# asu_racing_team_solo.net
KiCad netlist of a schematic drawn in Altium Designer
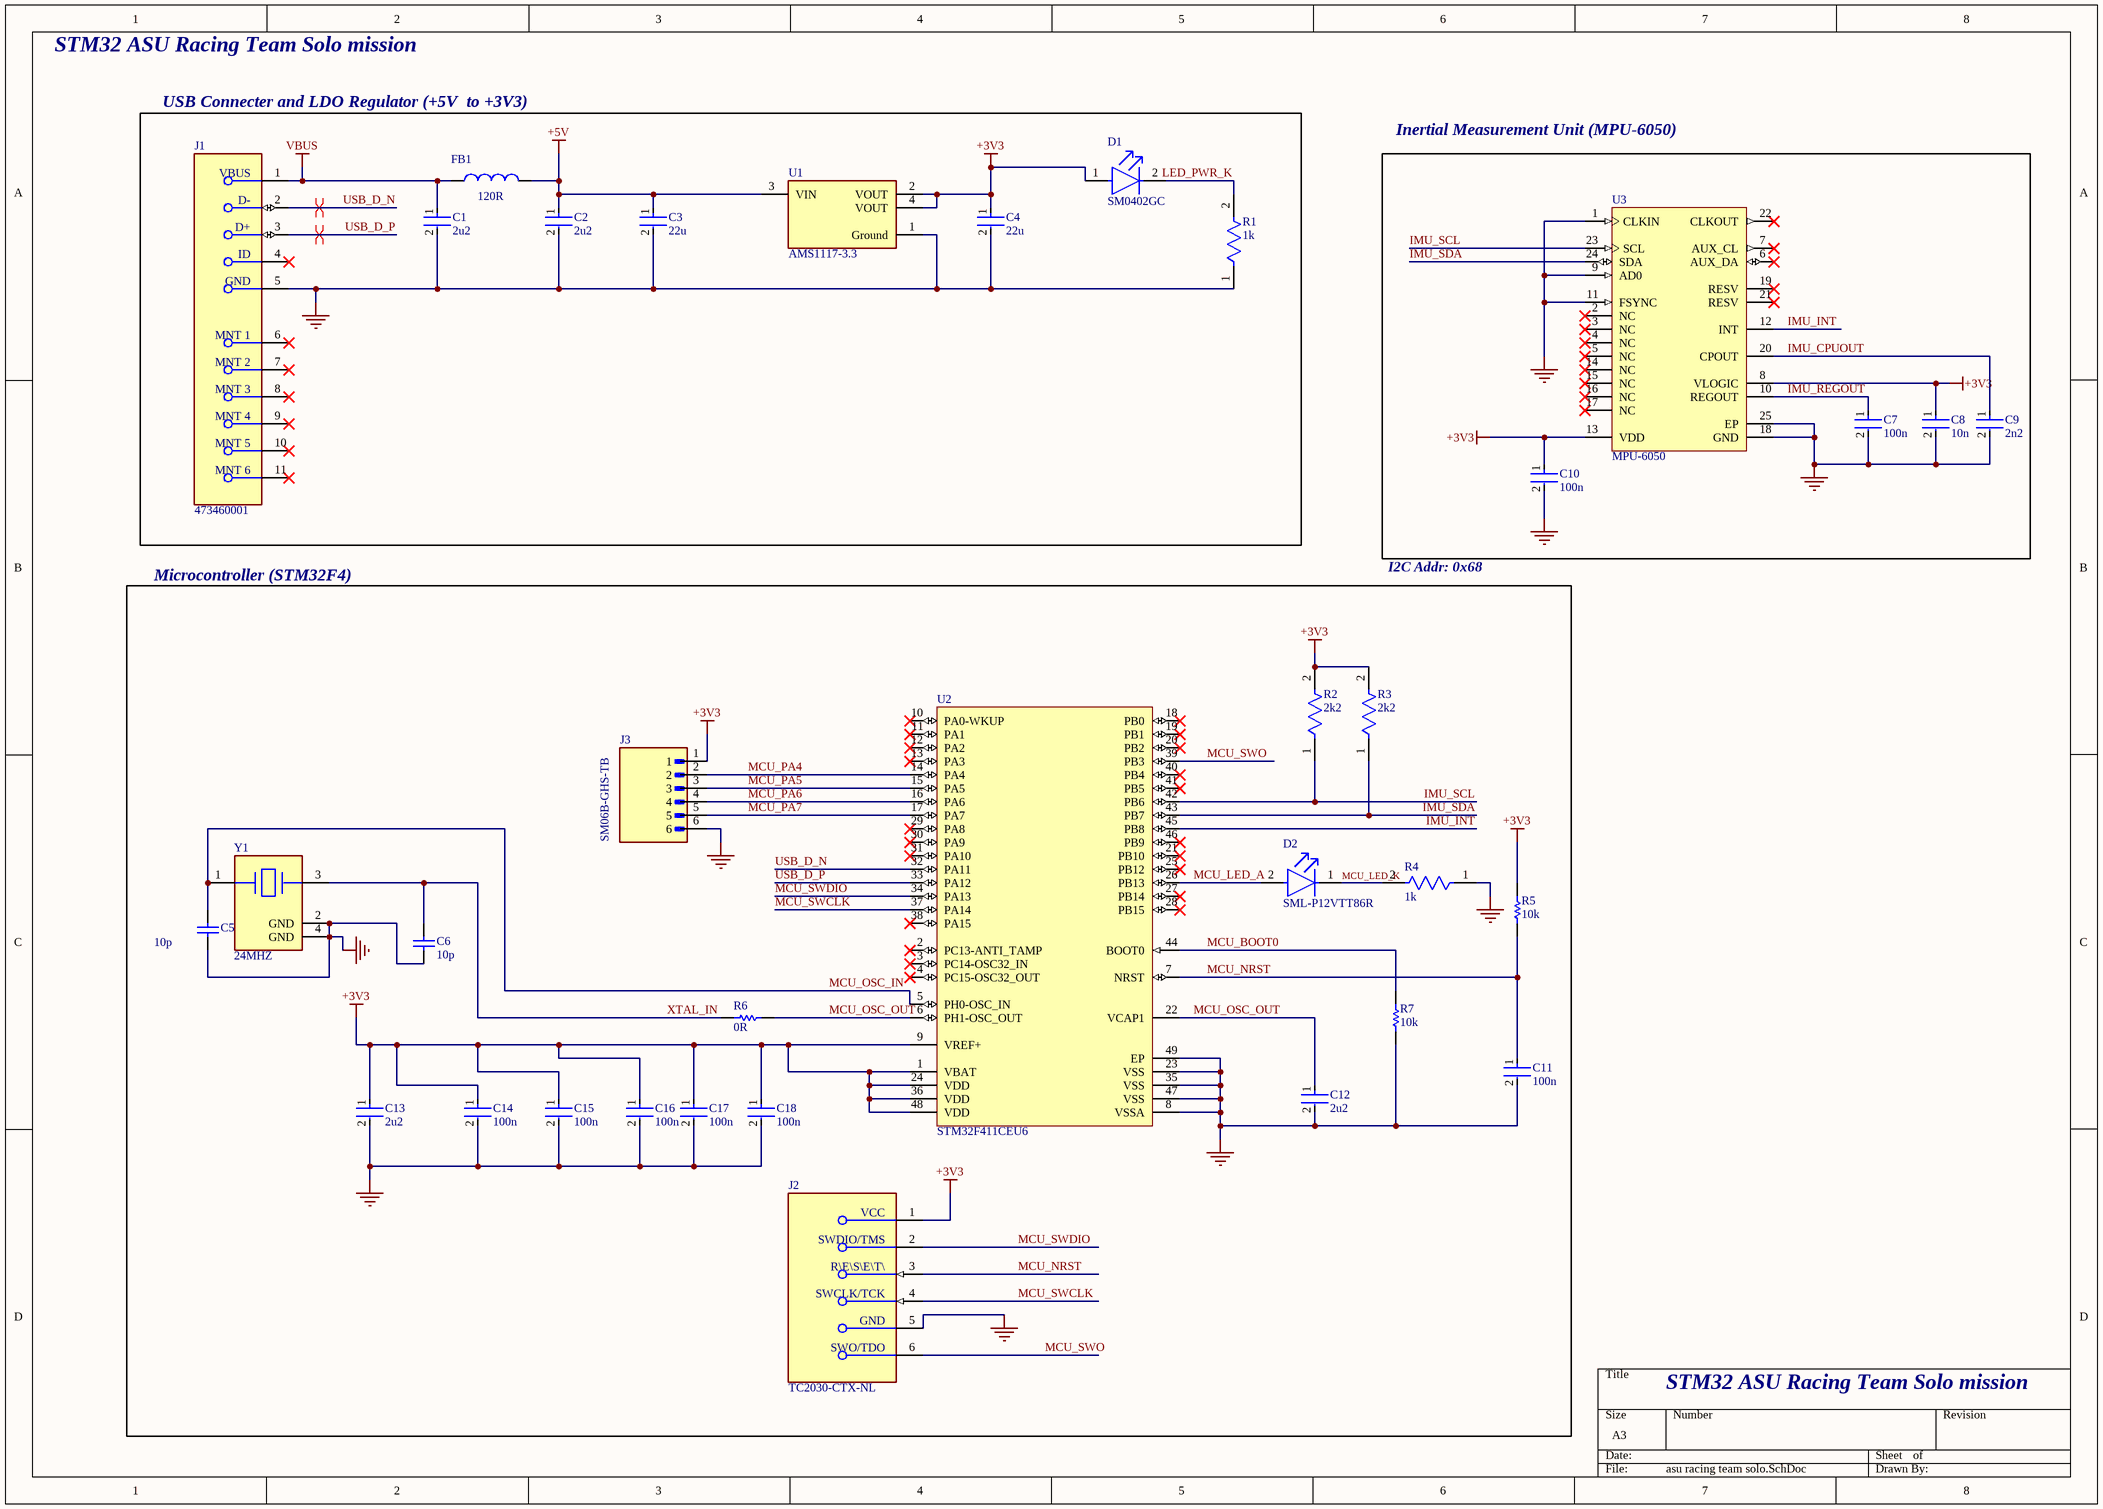
[diagram p0: asu racing team solo.SchDoc]

(export (version "E")
  (design (tool "Eeschema 10.0.6"))
  (components
    (comp (ref "C1")
      (value "2u2")
      (footprint "FP-C0603C-CF-MFG")
      (description "Capacitor; Ceramic; Cap; .100uF; Tol 10%; SMT; Vol-Rtg 16V; X7R; Tape and Reel")
      (fields
        (field (name "MANUFACTURER PART NUMBER") "C0603C104K4RACTU")
        (field (name "OCTOPART") "https://octopart.com/c0603c104k4ractu-kemet-93067")
      )
      (libsource (lib "Altium Content Vault") (part "b4654b650e69147ec39a6b967a45e02"))
    )
    (comp (ref "C2")
      (value "2u2")
      (footprint "FP-C0603C-CF-MFG")
      (description "Capacitor; Ceramic; Cap; .100uF; Tol 10%; SMT; Vol-Rtg 16V; X7R; Tape and Reel")
      (fields
        (field (name "MANUFACTURER PART NUMBER") "C0603C104K4RACTU")
        (field (name "OCTOPART") "https://octopart.com/c0603c104k4ractu-kemet-93067")
      )
      (libsource (lib "Altium Content Vault") (part "b4654b650e69147ec39a6b967a45e02"))
    )
    (comp (ref "C3")
      (value "22u")
      (footprint "FP-C0805C106K4PACTU-MFG")
      (description "CAP CER 10UF 16V X5R 0805")
      (fields (field (name "TOLERANCE") "10%") (field (name "VOLTAGE") "16V"))
      (libsource (lib "Altium Content Vault") (part "e9c51b7dd13d4faca003ae77663ab08"))
    )
    (comp (ref "C4")
      (value "22u")
      (footprint "FP-C0805C106K4PACTU-MFG")
      (description "CAP CER 10UF 16V X5R 0805")
      (fields (field (name "TOLERANCE") "10%") (field (name "VOLTAGE") "16V"))
      (libsource (lib "Altium Content Vault") (part "e9c51b7dd13d4faca003ae77663ab08"))
    )
    (comp (ref "C5")
      (value "10p")
      (footprint "CAPC1005X56X25ML10T15")
      (fields
        (field (name "MANUFACTURER") "AVX Interconnect / Elco")
        (field (name "PART NUMBER") "0402YC821KAT2A")
      )
      (libsource (lib "Altium Content Vault") (part "CAP"))
    )
    (comp (ref "C6")
      (value "10p")
      (footprint "CAPC1005X56X25ML10T15")
      (fields
        (field (name "MANUFACTURER") "AVX Interconnect / Elco")
        (field (name "PART NUMBER") "0402YC821KAT2A")
      )
      (libsource (lib "Altium Content Vault") (part "CAP"))
    )
    (comp (ref "C7")
      (value "100n")
      (footprint "FP-C0402-BB-MFG")
      (description "C0402 22 pF X7R 10.00% 16 V")
      (fields
        (field (name "TOLERANCE") "0.1")
        (field (name "OCTOPART") "https://octopart.com/c0402c220k4ractu-kemet-77858932")
      )
      (libsource (lib "Altium Content Vault") (part "b4654b650e69147ec39a6b967a45e02"))
    )
    (comp (ref "C8")
      (value "10n")
      (footprint "FP-C0402-BB-MFG")
      (description "C0402 22 pF X7R 10.00% 16 V")
      (fields
        (field (name "TOLERANCE") "0.1")
        (field (name "OCTOPART") "https://octopart.com/c0402c220k4ractu-kemet-77858932")
      )
      (libsource (lib "Altium Content Vault") (part "b4654b650e69147ec39a6b967a45e02"))
    )
    (comp (ref "C9")
      (value "2n2")
      (footprint "FP-C0402-BB-MFG")
      (description "C0402 22 pF X7R 10.00% 16 V")
      (fields
        (field (name "TOLERANCE") "0.1")
        (field (name "OCTOPART") "https://octopart.com/c0402c220k4ractu-kemet-77858932")
      )
      (libsource (lib "Altium Content Vault") (part "b4654b650e69147ec39a6b967a45e02"))
    )
    (comp (ref "C10")
      (value "100n")
      (footprint "FP-C0402-BB-MFG")
      (description "C0402 22 pF X7R 10.00% 16 V")
      (fields
        (field (name "TOLERANCE") "0.1")
        (field (name "OCTOPART") "https://octopart.com/c0402c220k4ractu-kemet-77858932")
      )
      (libsource (lib "Altium Content Vault") (part "b4654b650e69147ec39a6b967a45e02"))
    )
    (comp (ref "C11")
      (value "100n")
      (footprint "FP-C0402-BB-MFG")
      (description "C0402 22 pF X7R 10.00% 16 V")
      (fields
        (field (name "TOLERANCE") "0.1")
        (field (name "OCTOPART") "https://octopart.com/c0402c220k4ractu-kemet-77858932")
      )
      (libsource (lib "Altium Content Vault") (part "b4654b650e69147ec39a6b967a45e02"))
    )
    (comp (ref "C12")
      (value "2u2")
      (footprint "FP-C0603C-CF-MFG")
      (description "Capacitor; Ceramic; Cap; .100uF; Tol 10%; SMT; Vol-Rtg 16V; X7R; Tape and Reel")
      (fields
        (field (name "MANUFACTURER PART NUMBER") "C0603C104K4RACTU")
        (field (name "OCTOPART") "https://octopart.com/c0603c104k4ractu-kemet-93067")
      )
      (libsource (lib "Altium Content Vault") (part "b4654b650e69147ec39a6b967a45e02"))
    )
    (comp (ref "C13")
      (value "2u2")
      (footprint "FP-C0603C-CF-MFG")
      (description "Capacitor; Ceramic; Cap; .100uF; Tol 10%; SMT; Vol-Rtg 16V; X7R; Tape and Reel")
      (fields
        (field (name "MANUFACTURER PART NUMBER") "C0603C104K4RACTU")
        (field (name "OCTOPART") "https://octopart.com/c0603c104k4ractu-kemet-93067")
      )
      (libsource (lib "Altium Content Vault") (part "b4654b650e69147ec39a6b967a45e02"))
    )
    (comp (ref "C14")
      (value "100n")
      (footprint "FP-C0402-BB-MFG")
      (description "C0402 22 pF X7R 10.00% 16 V")
      (fields
        (field (name "TOLERANCE") "0.1")
        (field (name "OCTOPART") "https://octopart.com/c0402c220k4ractu-kemet-77858932")
      )
      (libsource (lib "Altium Content Vault") (part "b4654b650e69147ec39a6b967a45e02"))
    )
    (comp (ref "C15")
      (value "100n")
      (footprint "FP-C0402-BB-MFG")
      (description "C0402 22 pF X7R 10.00% 16 V")
      (fields
        (field (name "TOLERANCE") "0.1")
        (field (name "OCTOPART") "https://octopart.com/c0402c220k4ractu-kemet-77858932")
      )
      (libsource (lib "Altium Content Vault") (part "b4654b650e69147ec39a6b967a45e02"))
    )
    (comp (ref "C16")
      (value "100n")
      (footprint "FP-C0402-BB-MFG")
      (description "C0402 22 pF X7R 10.00% 16 V")
      (fields
        (field (name "TOLERANCE") "0.1")
        (field (name "OCTOPART") "https://octopart.com/c0402c220k4ractu-kemet-77858932")
      )
      (libsource (lib "Altium Content Vault") (part "b4654b650e69147ec39a6b967a45e02"))
    )
    (comp (ref "C17")
      (value "100n")
      (footprint "FP-C0402-BB-MFG")
      (description "C0402 22 pF X7R 10.00% 16 V")
      (fields
        (field (name "TOLERANCE") "0.1")
        (field (name "OCTOPART") "https://octopart.com/c0402c220k4ractu-kemet-77858932")
      )
      (libsource (lib "Altium Content Vault") (part "b4654b650e69147ec39a6b967a45e02"))
    )
    (comp (ref "C18")
      (value "100n")
      (footprint "FP-C0402-BB-MFG")
      (description "C0402 22 pF X7R 10.00% 16 V")
      (fields
        (field (name "TOLERANCE") "0.1")
        (field (name "OCTOPART") "https://octopart.com/c0402c220k4ractu-kemet-77858932")
      )
      (libsource (lib "Altium Content Vault") (part "b4654b650e69147ec39a6b967a45e02"))
    )
    (comp (ref "D1")
      (value "SM0402GC")
      (footprint "FP-SM0402GC-MFG")
      (description "LED GREEN CLEAR 0402 SMD")
      (libsource (lib "Altium Content Vault") (part "ab1c01a81903e929fc6c44469aada92"))
    )
    (comp (ref "D2")
      (value "SML-P12VTT86R")
      (footprint "FP-SML-P1-MFG")
      (description "LED RED CLEAR 0402 SMD")
      (fields
        (field (name "OCTOPART") "https://octopart.com/sml-p12vtt86r-rohm-34112315")
        (field (name "MANUFACTURER") "Rohm")
      )
      (libsource (lib "Altium Content Vault") (part "8706943c75ba83719d021d2fdc84c58"))
    )
    (comp (ref "FB1")
      (value "120R")
      (footprint "WE-CBF HF_0603_HC")
      (description "Ferrite Bead (emi Suppression), 1.6X0.8X0.8MM (0603), 600O Impedance At 100 Mhz")
      (fields (field (name "TOLERANCE") "25%"))
      (libsource (lib "Altium Content Vault") (part "Ferrite"))
    )
    (comp (ref "J1")
      (value "473460001")
      (footprint "FP-473460001-MFG")
      (description "CONN RCPT USB2.0 MICRO B SMD R/A")
      (fields
        (field (name "OCTOPART") "https://octopart.com/47346-0001-molex-7164928")
        (field (name "MANUFACTURER") "Molex")
      )
      (libsource (lib "Altium Content Vault") (part "53ae1f1d9b557310b43ca686e5bb76a"))
    )
    (comp (ref "J2")
      (value "TC2030-CTX-NL")
      (footprint "FP-TC2030-CTX-NL-MFG")
      (description "6-Pin “No legs” TC2030 Plug-of-Nails™ Cable for use with ARM Cortex processors")
      (libsource (lib "Altium Content Vault") (part "e3fe093a55dc37473f431e03719485e"))
    )
    (comp (ref "J3")
      (value "SM06B-GHS-TB")
      (footprint "JST_SM06B-GHS-TB")
      (description "Connector Header Surface Mount, Right Angle 6 position 0.049 (1.25mm)")
      (fields (field (name "MF") "JST Sales"))
      (libsource (lib "SM06B-GHS-TB") (part "SM06B-GHS-TB"))
    )
    (comp (ref "R1")
      (value "1k")
      (footprint "FP-RC0402-0_4-IPC_A")
      (description "RES 1K OHM 1% 1/16W 0402")
      (fields (field (name "TOLERANCE") "1%"))
      (libsource (lib "Altium Content Vault") (part "1029c3af85768c4190bb7ad29bc67b5"))
    )
    (comp (ref "R2")
      (value "2k2")
      (footprint "FP-RC0402-0_4-IPC_A")
      (description "RES 1K OHM 1% 1/16W 0402")
      (fields (field (name "TOLERANCE") "1%"))
      (libsource (lib "Altium Content Vault") (part "1029c3af85768c4190bb7ad29bc67b5"))
    )
    (comp (ref "R3")
      (value "2k2")
      (footprint "FP-RC0402-0_4-IPC_A")
      (description "RES 1K OHM 1% 1/16W 0402")
      (fields (field (name "TOLERANCE") "1%"))
      (libsource (lib "Altium Content Vault") (part "1029c3af85768c4190bb7ad29bc67b5"))
    )
    (comp (ref "R4")
      (value "1k")
      (footprint "FP-RC0402-0_4-IPC_A")
      (description "RES 1K OHM 1% 1/16W 0402")
      (fields (field (name "TOLERANCE") "1%"))
      (libsource (lib "Altium Content Vault") (part "1029c3af85768c4190bb7ad29bc67b5"))
    )
    (comp (ref "R5")
      (value "10k")
      (footprint "RESC1005X40X25LL05T10")
      (fields (field (name "PART NUMBER") "RC0402FR-0710KL") (field (name "MANUFACTURER") "Yageo / Phycomp"))
      (libsource (lib "Altium Content Vault") (part "RES"))
    )
    (comp (ref "R6")
      (value "0R")
      (footprint "RESC1005X40X25LL05T10")
      (fields (field (name "PART NUMBER") "RC0402FR-0710KL") (field (name "MANUFACTURER") "Yageo / Phycomp"))
      (libsource (lib "Altium Content Vault") (part "RES"))
    )
    (comp (ref "R7")
      (value "10k")
      (footprint "RESC1005X40X25LL05T10")
      (fields (field (name "PART NUMBER") "RC0402FR-0710KL") (field (name "MANUFACTURER") "Yageo / Phycomp"))
      (libsource (lib "Altium Content Vault") (part "RES"))
    )
    (comp (ref "U1")
      (value "AMS1117-3.3")
      (footprint "FP-AMS1117-IPC_C")
      (description "LDO Voltage Regulators 1A, 3.3V")
      (fields
        (field (name "OCTOPART") "https://octopart.com/ams1117-3.3-advanced+monolithic+systems-25899300")
        (field (name "MANUFACTURER") "Advanced Monolithic Systems")
      )
      (libsource (lib "Altium Content Vault") (part "8bdbb5f8e77002000e30dd2845d0354"))
    )
    (comp (ref "U2")
      (value "STM32F411CEU6")
      (footprint "STM-UFQFPN48_L")
      (libsource (lib "Altium Content Vault") (part "MC-ARM-STM32F411-UFQFPN48"))
    )
    (comp (ref "U3")
      (value "MPU-6050")
      (footprint "IS-QFN-24_V")
      (fields (field (name "MANUFACTURER") "InvenSense"))
      (libsource (lib "Altium Content Vault") (part "IS-MPU-6050-QFN-24"))
    )
    (comp (ref "Y1")
      (value "24MHZ")
      (footprint "FP-ABM8-MFG")
      (description "Crystal 24MHz ±20ppm 18pF SMD-4 3.2mm x 2.5mm")
      (fields (field (name "TOLERANCE") "20ppm"))
      (libsource (lib "Altium Content Vault") (part "dfdb7f9a12507849fb681da9a70121c"))
    )
  )
  (nets
    (net (code "1") (name "+3V3") (class "Default")
      (node (ref "C10") (pin "1") (pinfunction "1_1") (pintype "passive"))
      (node (ref "C13") (pin "1") (pinfunction "1_1") (pintype "passive"))
      (node (ref "C14") (pin "1") (pinfunction "1_1") (pintype "passive"))
      (node (ref "C15") (pin "1") (pinfunction "1_1") (pintype "passive"))
      (node (ref "C16") (pin "1") (pinfunction "1_1") (pintype "passive"))
      (node (ref "C17") (pin "1") (pinfunction "1_1") (pintype "passive"))
      (node (ref "C18") (pin "1") (pinfunction "1_1") (pintype "passive"))
      (node (ref "C4") (pin "1") (pinfunction "1_1") (pintype "passive"))
      (node (ref "C8") (pin "1") (pinfunction "1_1") (pintype "passive"))
      (node (ref "D1") (pin "1") (pinfunction "A_1") (pintype "passive"))
      (node (ref "J2") (pin "1") (pinfunction "VCC_1") (pintype "power_in"))
      (node (ref "J3") (pin "1") (pinfunction "1_1") (pintype "passive"))
      (node (ref "R2") (pin "2") (pinfunction "2_2") (pintype "passive"))
      (node (ref "R3") (pin "2") (pinfunction "2_2") (pintype "passive"))
      (node (ref "R5") (pin "2") (pinfunction "2_2") (pintype "passive"))
      (node (ref "U1") (pin "2") (pinfunction "VOUT_2") (pintype "passive"))
      (node (ref "U1") (pin "4") (pinfunction "VOUT_4") (pintype "passive"))
      (node (ref "U2") (pin "1") (pinfunction "VBAT_1") (pintype "power_in"))
      (node (ref "U2") (pin "24") (pinfunction "VDD_24") (pintype "power_in"))
      (node (ref "U2") (pin "36") (pinfunction "VDD_36") (pintype "power_in"))
      (node (ref "U2") (pin "48") (pinfunction "VDD_48") (pintype "power_in"))
      (node (ref "U2") (pin "9") (pinfunction "VREF+_9") (pintype "power_in"))
      (node (ref "U3") (pin "13") (pinfunction "VDD_13") (pintype "power_in"))
      (node (ref "U3") (pin "8") (pinfunction "VLOGIC_8") (pintype "power_in"))
    )
    (net (code "2") (name "+5V") (class "Default")
      (node (ref "C2") (pin "1") (pinfunction "1_1") (pintype "passive"))
      (node (ref "C3") (pin "1") (pinfunction "1_1") (pintype "passive"))
      (node (ref "FB1") (pin "2") (pinfunction "2_2") (pintype "passive"))
      (node (ref "U1") (pin "3") (pinfunction "VIN_3") (pintype "power_in"))
    )
    (net (code "3") (name "/IMU_CPUOUT") (class "Default")
      (node (ref "C9") (pin "1") (pinfunction "1_1") (pintype "passive"))
      (node (ref "U3") (pin "20") (pinfunction "CPOUT_20") (pintype "passive"))
    )
    (net (code "4") (name "/IMU_INT") (class "Default")
      (node (ref "U2") (pin "45") (pinfunction "PB8_45") (pintype "bidirectional"))
      (node (ref "U3") (pin "12") (pinfunction "INT_12") (pintype "open_collector"))
    )
    (net (code "5") (name "/IMU_REGOUT") (class "Default")
      (node (ref "C7") (pin "1") (pinfunction "1_1") (pintype "passive"))
      (node (ref "U3") (pin "10") (pinfunction "REGOUT_10") (pintype "passive"))
    )
    (net (code "6") (name "/IMU_SCL") (class "Default")
      (node (ref "R2") (pin "1") (pinfunction "1_1") (pintype "passive"))
      (node (ref "U2") (pin "42") (pinfunction "PB6_42") (pintype "bidirectional"))
      (node (ref "U3") (pin "23") (pinfunction "SCL_23") (pintype "input"))
    )
    (net (code "7") (name "/IMU_SDA") (class "Default")
      (node (ref "R3") (pin "1") (pinfunction "1_1") (pintype "passive"))
      (node (ref "U2") (pin "43") (pinfunction "PB7_43") (pintype "bidirectional"))
      (node (ref "U3") (pin "24") (pinfunction "SDA_24") (pintype "bidirectional"))
    )
    (net (code "8") (name "/LED_PWR_K") (class "Default")
      (node (ref "D1") (pin "2") (pinfunction "C_2") (pintype "passive"))
      (node (ref "R1") (pin "2") (pinfunction "2_2") (pintype "passive"))
    )
    (net (code "9") (name "/MCU_BOOT0") (class "Default")
      (node (ref "R7") (pin "2") (pinfunction "2_2") (pintype "passive"))
      (node (ref "U2") (pin "44") (pinfunction "BOOT0_44") (pintype "input"))
    )
    (net (code "10") (name "/MCU_LED_A") (class "Default")
      (node (ref "D2") (pin "2") (pinfunction "A_2") (pintype "passive"))
      (node (ref "U2") (pin "26") (pinfunction "PB13_26") (pintype "bidirectional"))
    )
    (net (code "11") (name "/MCU_LED_K") (class "Default")
      (node (ref "D2") (pin "1") (pinfunction "C_1") (pintype "passive"))
      (node (ref "R4") (pin "2") (pinfunction "2_2") (pintype "passive"))
    )
    (net (code "12") (name "/MCU_NRST") (class "Default")
      (node (ref "C11") (pin "1") (pinfunction "1_1") (pintype "passive"))
      (node (ref "J2") (pin "3") (pinfunction "~{RESET}_3") (pintype "input"))
      (node (ref "R5") (pin "1") (pinfunction "1_1") (pintype "passive"))
      (node (ref "U2") (pin "7") (pinfunction "NRST_7") (pintype "bidirectional"))
    )
    (net (code "13") (name "/MCU_OSC_IN") (class "Default")
      (node (ref "C5") (pin "2") (pinfunction "2_2") (pintype "passive"))
      (node (ref "U2") (pin "5") (pinfunction "PH0-OSC_IN_5") (pintype "bidirectional"))
      (node (ref "Y1") (pin "1") (pinfunction "1_1") (pintype "passive"))
    )
    (net (code "14") (name "/MCU_OSC_OUT") (class "Default")
      (node (ref "C12") (pin "1") (pinfunction "1_1") (pintype "passive"))
      (node (ref "R6") (pin "2") (pinfunction "2_2") (pintype "passive"))
      (node (ref "U2") (pin "22") (pinfunction "VCAP1_22") (pintype "passive"))
      (node (ref "U2") (pin "6") (pinfunction "PH1-OSC_OUT_6") (pintype "bidirectional"))
    )
    (net (code "15") (name "/MCU_PA4") (class "Default")
      (node (ref "J3") (pin "2") (pinfunction "2_2") (pintype "passive"))
      (node (ref "U2") (pin "14") (pinfunction "PA4_14") (pintype "bidirectional"))
    )
    (net (code "16") (name "/MCU_PA5") (class "Default")
      (node (ref "J3") (pin "3") (pinfunction "3_3") (pintype "passive"))
      (node (ref "U2") (pin "15") (pinfunction "PA5_15") (pintype "bidirectional"))
    )
    (net (code "17") (name "/MCU_PA6") (class "Default")
      (node (ref "J3") (pin "4") (pinfunction "4_4") (pintype "passive"))
      (node (ref "U2") (pin "16") (pinfunction "PA6_16") (pintype "bidirectional"))
    )
    (net (code "18") (name "/MCU_PA7") (class "Default")
      (node (ref "J3") (pin "5") (pinfunction "5_5") (pintype "passive"))
      (node (ref "U2") (pin "17") (pinfunction "PA7_17") (pintype "bidirectional"))
    )
    (net (code "19") (name "/MCU_SWCLK") (class "Default")
      (node (ref "J2") (pin "4") (pinfunction "SWCLK/TCK_4") (pintype "input"))
      (node (ref "U2") (pin "37") (pinfunction "PA14_37") (pintype "bidirectional"))
    )
    (net (code "20") (name "/MCU_SWDIO") (class "Default")
      (node (ref "J2") (pin "2") (pinfunction "SWDIO/TMS_2") (pintype "passive"))
      (node (ref "U2") (pin "34") (pinfunction "PA13_34") (pintype "bidirectional"))
    )
    (net (code "21") (name "/MCU_SWO") (class "Default")
      (node (ref "J2") (pin "6") (pinfunction "SWO/TDO_6") (pintype "passive"))
      (node (ref "U2") (pin "39") (pinfunction "PB3_39") (pintype "bidirectional"))
    )
    (net (code "22") (name "/USB_D_N") (class "Default")
      (node (ref "J1") (pin "2") (pinfunction "D-_2") (pintype "bidirectional"))
      (node (ref "U2") (pin "32") (pinfunction "PA11_32") (pintype "bidirectional"))
    )
    (net (code "23") (name "/USB_D_P") (class "Default")
      (node (ref "J1") (pin "3") (pinfunction "D+_3") (pintype "bidirectional"))
      (node (ref "U2") (pin "33") (pinfunction "PA12_33") (pintype "bidirectional"))
    )
    (net (code "24") (name "/XTAL_IN") (class "Default")
      (node (ref "C6") (pin "2") (pinfunction "2_2") (pintype "passive"))
      (node (ref "R6") (pin "1") (pinfunction "1_1") (pintype "passive"))
      (node (ref "Y1") (pin "3") (pinfunction "3_3") (pintype "passive"))
    )
    (net (code "25") (name "GND") (class "Default")
      (node (ref "C1") (pin "2") (pinfunction "2_2") (pintype "passive"))
      (node (ref "C10") (pin "2") (pinfunction "2_2") (pintype "passive"))
      (node (ref "C11") (pin "2") (pinfunction "2_2") (pintype "passive"))
      (node (ref "C12") (pin "2") (pinfunction "2_2") (pintype "passive"))
      (node (ref "C13") (pin "2") (pinfunction "2_2") (pintype "passive"))
      (node (ref "C14") (pin "2") (pinfunction "2_2") (pintype "passive"))
      (node (ref "C15") (pin "2") (pinfunction "2_2") (pintype "passive"))
      (node (ref "C16") (pin "2") (pinfunction "2_2") (pintype "passive"))
      (node (ref "C17") (pin "2") (pinfunction "2_2") (pintype "passive"))
      (node (ref "C18") (pin "2") (pinfunction "2_2") (pintype "passive"))
      (node (ref "C2") (pin "2") (pinfunction "2_2") (pintype "passive"))
      (node (ref "C3") (pin "2") (pinfunction "2_2") (pintype "passive"))
      (node (ref "C4") (pin "2") (pinfunction "2_2") (pintype "passive"))
      (node (ref "C5") (pin "1") (pinfunction "1_1") (pintype "passive"))
      (node (ref "C6") (pin "1") (pinfunction "1_1") (pintype "passive"))
      (node (ref "C7") (pin "2") (pinfunction "2_2") (pintype "passive"))
      (node (ref "C8") (pin "2") (pinfunction "2_2") (pintype "passive"))
      (node (ref "C9") (pin "2") (pinfunction "2_2") (pintype "passive"))
      (node (ref "J1") (pin "5") (pinfunction "GND_5") (pintype "power_in"))
      (node (ref "J2") (pin "5") (pinfunction "GND_5") (pintype "power_in"))
      (node (ref "J3") (pin "6") (pinfunction "6_6") (pintype "passive"))
      (node (ref "R1") (pin "1") (pinfunction "1_1") (pintype "passive"))
      (node (ref "R4") (pin "1") (pinfunction "1_1") (pintype "passive"))
      (node (ref "R7") (pin "1") (pinfunction "1_1") (pintype "passive"))
      (node (ref "U1") (pin "1") (pinfunction "Ground_1") (pintype "power_in"))
      (node (ref "U2") (pin "23") (pinfunction "VSS_23") (pintype "power_in"))
      (node (ref "U2") (pin "35") (pinfunction "VSS_35") (pintype "power_in"))
      (node (ref "U2") (pin "47") (pinfunction "VSS_47") (pintype "power_in"))
      (node (ref "U2") (pin "49") (pinfunction "EP_49") (pintype "power_in"))
      (node (ref "U2") (pin "8") (pinfunction "VSSA_8") (pintype "power_in"))
      (node (ref "U3") (pin "1") (pinfunction "CLKIN_1") (pintype "input"))
      (node (ref "U3") (pin "11") (pinfunction "FSYNC_11") (pintype "input"))
      (node (ref "U3") (pin "18") (pinfunction "GND_18") (pintype "power_in"))
      (node (ref "U3") (pin "25") (pinfunction "EP_25") (pintype "power_in"))
      (node (ref "U3") (pin "9") (pinfunction "AD0_9") (pintype "input"))
      (node (ref "Y1") (pin "2") (pinfunction "GND_2") (pintype "power_in"))
      (node (ref "Y1") (pin "4") (pinfunction "GND_4") (pintype "power_in"))
    )
    (net (code "26") (name "VBUS") (class "Default")
      (node (ref "C1") (pin "1") (pinfunction "1_1") (pintype "passive"))
      (node (ref "FB1") (pin "1") (pinfunction "1_1") (pintype "passive"))
      (node (ref "J1") (pin "1") (pinfunction "VBUS_1") (pintype "power_in"))
    )
    (net (code "27") (name "unconnected-(J1-ID-Pad4)") (class "Default")
      (node (ref "J1") (pin "4") (pinfunction "ID_4") (pintype "passive+no_connect"))
    )
    (net (code "28") (name "unconnected-(J1-MNT_1-Pad6)") (class "Default")
      (node (ref "J1") (pin "6") (pinfunction "MNT_1_6") (pintype "passive+no_connect"))
    )
    (net (code "29") (name "unconnected-(J1-MNT_2-Pad7)") (class "Default")
      (node (ref "J1") (pin "7") (pinfunction "MNT_2_7") (pintype "passive+no_connect"))
    )
    (net (code "30") (name "unconnected-(J1-MNT_3-Pad8)") (class "Default")
      (node (ref "J1") (pin "8") (pinfunction "MNT_3_8") (pintype "passive+no_connect"))
    )
    (net (code "31") (name "unconnected-(J1-MNT_4-Pad9)") (class "Default")
      (node (ref "J1") (pin "9") (pinfunction "MNT_4_9") (pintype "passive+no_connect"))
    )
    (net (code "32") (name "unconnected-(J1-MNT_5-Pad10)") (class "Default")
      (node (ref "J1") (pin "10") (pinfunction "MNT_5_10") (pintype "passive+no_connect"))
    )
    (net (code "33") (name "unconnected-(J1-MNT_6-Pad11)") (class "Default")
      (node (ref "J1") (pin "11") (pinfunction "MNT_6_11") (pintype "passive+no_connect"))
    )
    (net (code "34") (name "unconnected-(U2-PA0-WKUP-Pad10)") (class "Default")
      (node (ref "U2") (pin "10") (pinfunction "PA0-WKUP_10") (pintype "bidirectional+no_connect"))
    )
    (net (code "35") (name "unconnected-(U2-PA1-Pad11)") (class "Default")
      (node (ref "U2") (pin "11") (pinfunction "PA1_11") (pintype "bidirectional+no_connect"))
    )
    (net (code "36") (name "unconnected-(U2-PA2-Pad12)") (class "Default")
      (node (ref "U2") (pin "12") (pinfunction "PA2_12") (pintype "bidirectional+no_connect"))
    )
    (net (code "37") (name "unconnected-(U2-PA3-Pad13)") (class "Default")
      (node (ref "U2") (pin "13") (pinfunction "PA3_13") (pintype "bidirectional+no_connect"))
    )
    (net (code "38") (name "unconnected-(U2-PA8-Pad29)") (class "Default")
      (node (ref "U2") (pin "29") (pinfunction "PA8_29") (pintype "bidirectional+no_connect"))
    )
    (net (code "39") (name "unconnected-(U2-PA9-Pad30)") (class "Default")
      (node (ref "U2") (pin "30") (pinfunction "PA9_30") (pintype "bidirectional+no_connect"))
    )
    (net (code "40") (name "unconnected-(U2-PA10-Pad31)") (class "Default")
      (node (ref "U2") (pin "31") (pinfunction "PA10_31") (pintype "bidirectional+no_connect"))
    )
    (net (code "41") (name "unconnected-(U2-PA15-Pad38)") (class "Default")
      (node (ref "U2") (pin "38") (pinfunction "PA15_38") (pintype "bidirectional+no_connect"))
    )
    (net (code "42") (name "unconnected-(U2-PB0-Pad18)") (class "Default")
      (node (ref "U2") (pin "18") (pinfunction "PB0_18") (pintype "bidirectional+no_connect"))
    )
    (net (code "43") (name "unconnected-(U2-PB1-Pad19)") (class "Default")
      (node (ref "U2") (pin "19") (pinfunction "PB1_19") (pintype "bidirectional+no_connect"))
    )
    (net (code "44") (name "unconnected-(U2-PB2-Pad20)") (class "Default")
      (node (ref "U2") (pin "20") (pinfunction "PB2_20") (pintype "bidirectional+no_connect"))
    )
    (net (code "45") (name "unconnected-(U2-PB4-Pad40)") (class "Default")
      (node (ref "U2") (pin "40") (pinfunction "PB4_40") (pintype "bidirectional+no_connect"))
    )
    (net (code "46") (name "unconnected-(U2-PB5-Pad41)") (class "Default")
      (node (ref "U2") (pin "41") (pinfunction "PB5_41") (pintype "bidirectional+no_connect"))
    )
    (net (code "47") (name "unconnected-(U2-PB9-Pad46)") (class "Default")
      (node (ref "U2") (pin "46") (pinfunction "PB9_46") (pintype "bidirectional+no_connect"))
    )
    (net (code "48") (name "unconnected-(U2-PB10-Pad21)") (class "Default")
      (node (ref "U2") (pin "21") (pinfunction "PB10_21") (pintype "bidirectional+no_connect"))
    )
    (net (code "49") (name "unconnected-(U2-PB12-Pad25)") (class "Default")
      (node (ref "U2") (pin "25") (pinfunction "PB12_25") (pintype "bidirectional+no_connect"))
    )
    (net (code "50") (name "unconnected-(U2-PB14-Pad27)") (class "Default")
      (node (ref "U2") (pin "27") (pinfunction "PB14_27") (pintype "bidirectional+no_connect"))
    )
    (net (code "51") (name "unconnected-(U2-PB15-Pad28)") (class "Default")
      (node (ref "U2") (pin "28") (pinfunction "PB15_28") (pintype "bidirectional+no_connect"))
    )
    (net (code "52") (name "unconnected-(U2-PC13-ANTI_TAMP-Pad2)") (class "Default")
      (node (ref "U2") (pin "2") (pinfunction "PC13-ANTI_TAMP_2") (pintype "bidirectional+no_connect"))
    )
    (net (code "53") (name "unconnected-(U2-PC14-OSC32_IN-Pad3)") (class "Default")
      (node (ref "U2") (pin "3") (pinfunction "PC14-OSC32_IN_3") (pintype "bidirectional+no_connect"))
    )
    (net (code "54") (name "unconnected-(U2-PC15-OSC32_OUT-Pad4)") (class "Default")
      (node (ref "U2") (pin "4") (pinfunction "PC15-OSC32_OUT_4") (pintype "bidirectional+no_connect"))
    )
    (net (code "55") (name "unconnected-(U3-AUX_CL-Pad7)") (class "Default")
      (node (ref "U3") (pin "7") (pinfunction "AUX_CL_7") (pintype "output+no_connect"))
    )
    (net (code "56") (name "unconnected-(U3-AUX_DA-Pad6)") (class "Default")
      (node (ref "U3") (pin "6") (pinfunction "AUX_DA_6") (pintype "bidirectional+no_connect"))
    )
    (net (code "57") (name "unconnected-(U3-CLKOUT-Pad22)") (class "Default")
      (node (ref "U3") (pin "22") (pinfunction "CLKOUT_22") (pintype "output+no_connect"))
    )
    (net (code "58") (name "unconnected-(U3-NC-Pad2)") (class "Default")
      (node (ref "U3") (pin "2") (pinfunction "NC_2") (pintype "passive+no_connect"))
    )
    (net (code "59") (name "unconnected-(U3-NC-Pad3)") (class "Default")
      (node (ref "U3") (pin "3") (pinfunction "NC_3") (pintype "passive+no_connect"))
    )
    (net (code "60") (name "unconnected-(U3-NC-Pad4)") (class "Default")
      (node (ref "U3") (pin "4") (pinfunction "NC_4") (pintype "passive+no_connect"))
    )
    (net (code "61") (name "unconnected-(U3-NC-Pad5)") (class "Default")
      (node (ref "U3") (pin "5") (pinfunction "NC_5") (pintype "passive+no_connect"))
    )
    (net (code "62") (name "unconnected-(U3-NC-Pad14)") (class "Default")
      (node (ref "U3") (pin "14") (pinfunction "NC_14") (pintype "passive+no_connect"))
    )
    (net (code "63") (name "unconnected-(U3-NC-Pad15)") (class "Default")
      (node (ref "U3") (pin "15") (pinfunction "NC_15") (pintype "passive+no_connect"))
    )
    (net (code "64") (name "unconnected-(U3-NC-Pad16)") (class "Default")
      (node (ref "U3") (pin "16") (pinfunction "NC_16") (pintype "passive+no_connect"))
    )
    (net (code "65") (name "unconnected-(U3-NC-Pad17)") (class "Default")
      (node (ref "U3") (pin "17") (pinfunction "NC_17") (pintype "passive+no_connect"))
    )
    (net (code "66") (name "unconnected-(U3-RESV-Pad19)") (class "Default")
      (node (ref "U3") (pin "19") (pinfunction "RESV_19") (pintype "passive+no_connect"))
    )
    (net (code "67") (name "unconnected-(U3-RESV-Pad21)") (class "Default")
      (node (ref "U3") (pin "21") (pinfunction "RESV_21") (pintype "passive+no_connect"))
    )
  )
)
